# untitled.net
KiCad netlist of a schematic drawn in EAGLE
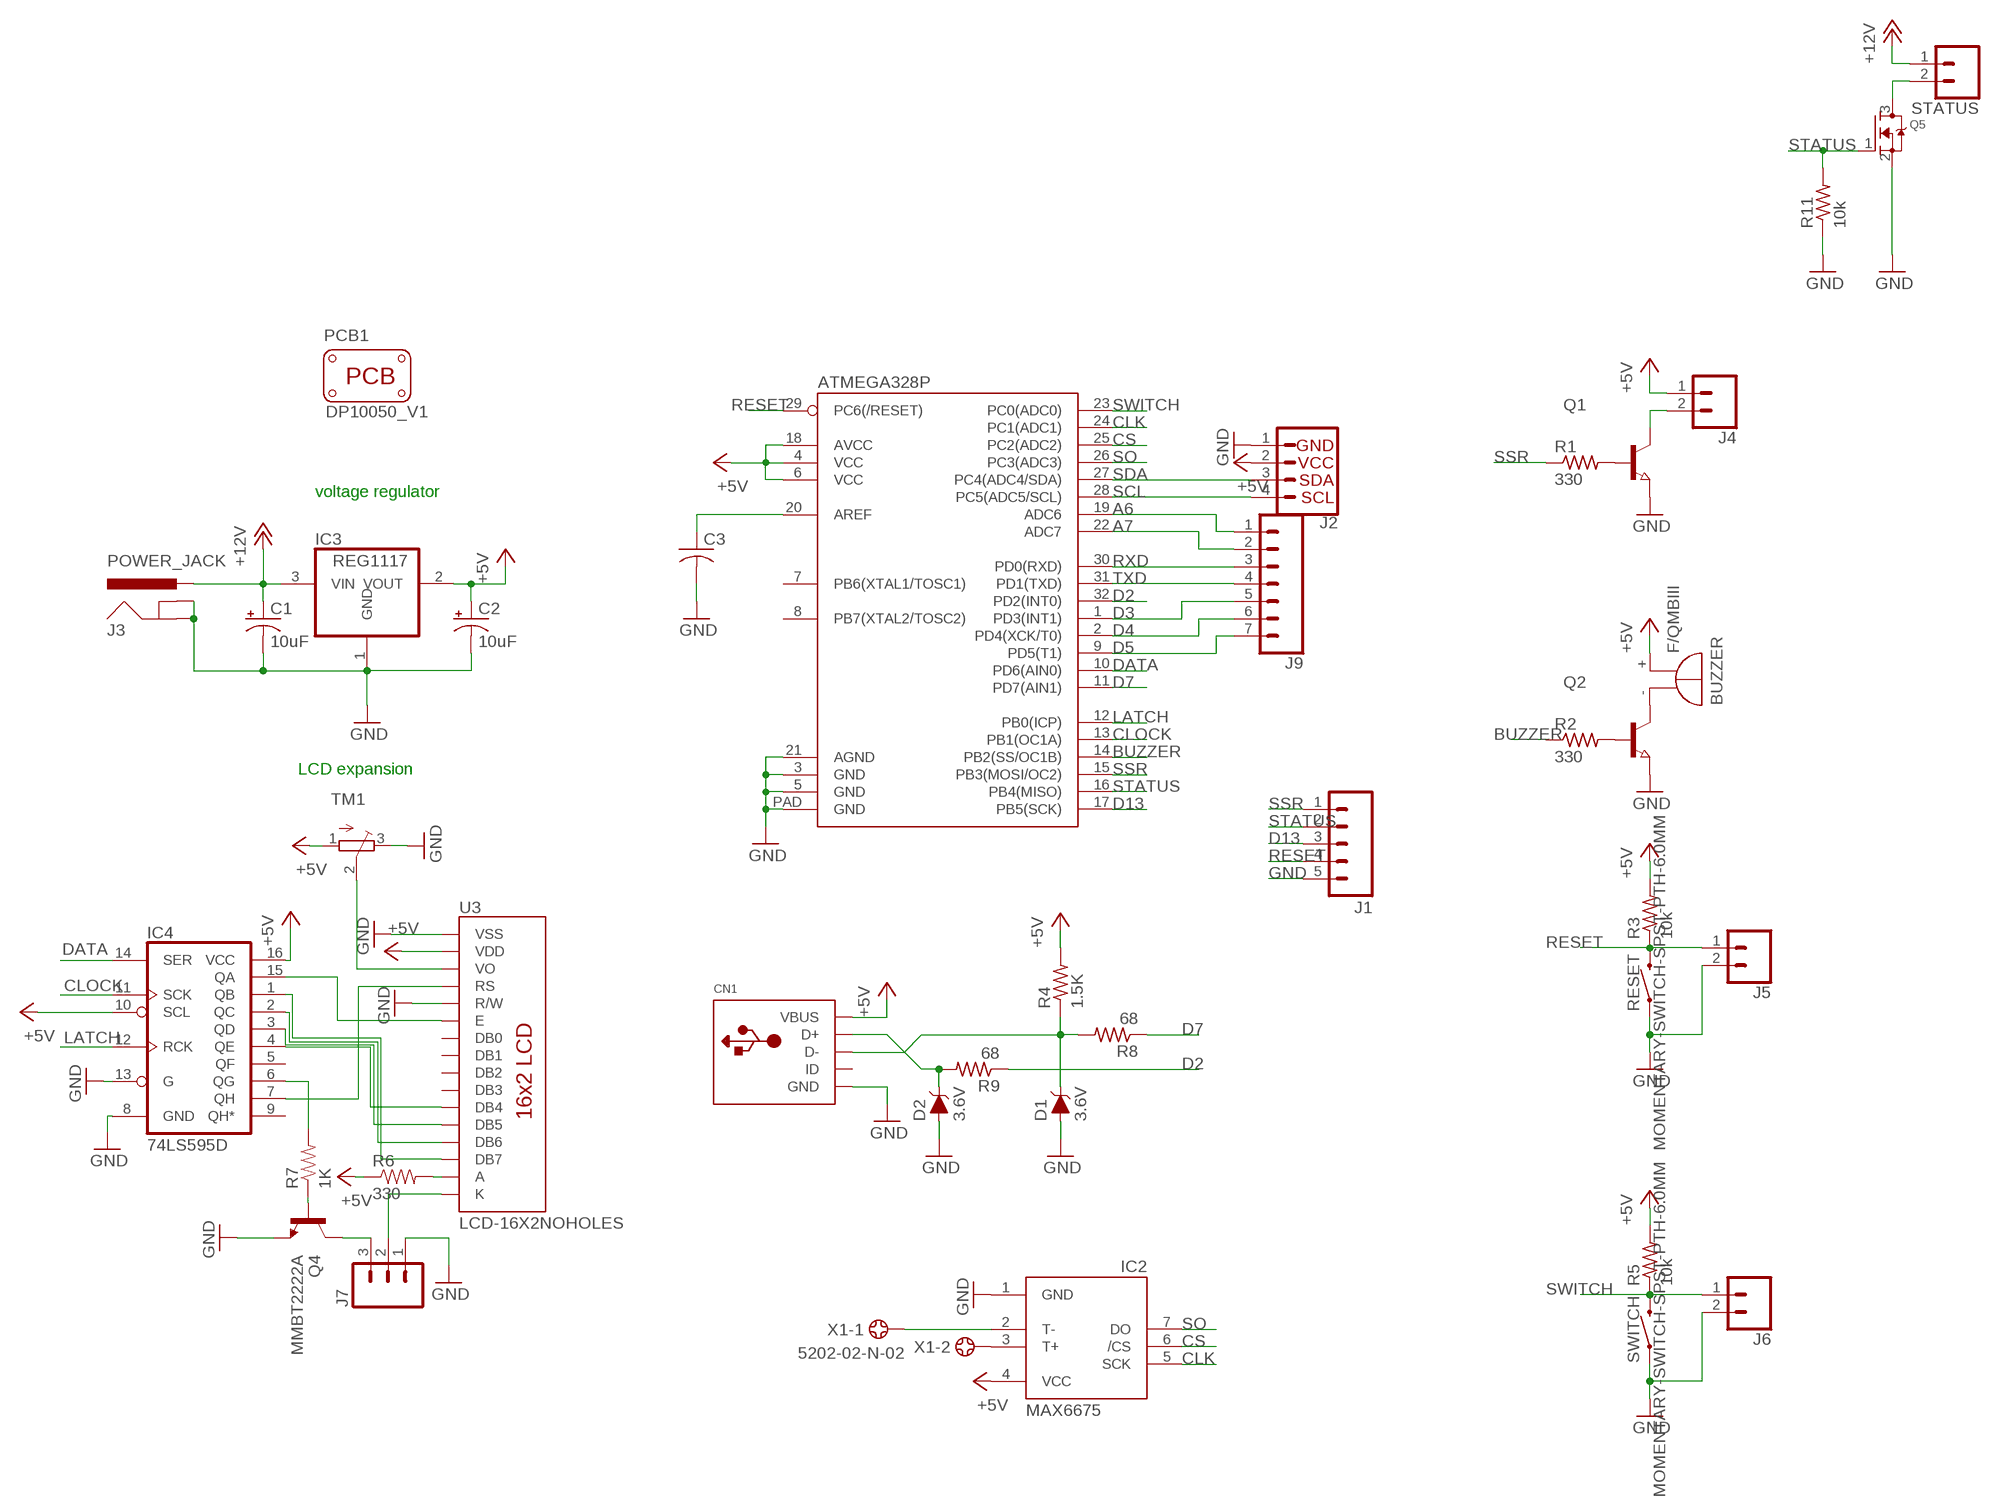
[diagram p0: schematic, sheet 1]

(export (version "E")
  (design (tool "Eeschema 10.0.6"))
  (components
    (comp (ref "ATMEGA328P")
      (value "ATMEGA328P_MLFMLF32")
      (footprint "eagle-import:MLF32-PAD")
      (libsource (lib "eagle-import") (part "ATMEGA328P_MLFMLF32"))
    )
    (comp (ref "BUZZER")
      (value "F/QMBIII")
      (footprint "eagle-import:F_QMBIII")
      (libsource (lib "eagle-import") (part "F/QMBIII"))
    )
    (comp (ref "C1")
      (value "10uF")
      (footprint "eagle-import:CT3216")
      (libsource (lib "eagle-import") (part "CPOL-USCT3216"))
    )
    (comp (ref "C2")
      (value "10uF")
      (footprint "eagle-import:CT3216")
      (libsource (lib "eagle-import") (part "CPOL-USCT3216"))
    )
    (comp (ref "C3")
      (value "C-USC0603")
      (footprint "eagle-import:C0603")
      (libsource (lib "eagle-import") (part "C-USC0603"))
    )
    (comp (ref "CN1")
      (value "USBMINIB")
      (footprint "eagle-import:USB-MINIB")
      (libsource (lib "eagle-import") (part "USBMINIB"))
    )
    (comp (ref "D1")
      (value "3.6V")
      (footprint "eagle-import:SOD-323")
      (libsource (lib "eagle-import") (part "DIODE-ZENER-BZT52C3V6S"))
    )
    (comp (ref "D2")
      (value "3.6V")
      (footprint "eagle-import:SOD-323")
      (libsource (lib "eagle-import") (part "DIODE-ZENER-BZT52C3V6S"))
    )
    (comp (ref "IC2")
      (value "MAX6675")
      (footprint "eagle-import:SO08")
      (libsource (lib "eagle-import") (part "MAX6675"))
    )
    (comp (ref "IC3")
      (value "REG1117")
      (footprint "eagle-import:SOT223")
      (libsource (lib "eagle-import") (part "REG1117"))
    )
    (comp (ref "IC4")
      (value "74LS595D")
      (footprint "eagle-import:SO16")
      (libsource (lib "eagle-import") (part "74595DLS"))
    )
    (comp (ref "J1")
      (value "M051.27MM")
      (footprint "eagle-import:1X05-1.27MM")
      (libsource (lib "eagle-import") (part "M051.27MM"))
    )
    (comp (ref "J2")
      (value "I2C_STANDARD")
      (footprint "eagle-import:1X04")
      (libsource (lib "eagle-import") (part "I2C_STANDARD"))
    )
    (comp (ref "J3")
      (value "POWER_JACK")
      (footprint "eagle-import:POWER_JACK_PTH")
      (libsource (lib "eagle-import") (part "POWER_JACK"))
    )
    (comp (ref "J4")
      (value "CONN_02")
      (footprint "eagle-import:1X02")
      (libsource (lib "eagle-import") (part "CONN_02"))
    )
    (comp (ref "J5")
      (value "CONN_02")
      (footprint "eagle-import:1X02")
      (libsource (lib "eagle-import") (part "CONN_02"))
    )
    (comp (ref "J6")
      (value "CONN_02")
      (footprint "eagle-import:1X02")
      (libsource (lib "eagle-import") (part "CONN_02"))
    )
    (comp (ref "J7")
      (value "M03PTH")
      (footprint "eagle-import:1X03")
      (libsource (lib "eagle-import") (part "M03PTH"))
    )
    (comp (ref "J9")
      (value "CONN_07")
      (footprint "eagle-import:1X07")
      (libsource (lib "eagle-import") (part "CONN_07"))
    )
    (comp (ref "PCB1")
      (value "PCB_DP_RECTANGLE-50X100")
      (footprint "eagle-import:DP10050_V1")
      (libsource (lib "eagle-import") (part "PCB_DP_RECTANGLE-50X100"))
    )
    (comp (ref "Q1")
      (value "NPN-TRANSISTOR_SOT23")
      (footprint "eagle-import:SOT23")
      (libsource (lib "eagle-import") (part "NPN-TRANSISTOR_SOT23"))
    )
    (comp (ref "Q2")
      (value "NPN-TRANSISTOR_SOT23")
      (footprint "eagle-import:SOT23")
      (libsource (lib "eagle-import") (part "NPN-TRANSISTOR_SOT23"))
    )
    (comp (ref "Q4")
      (value "MMBT2222A")
      (footprint "eagle-import:SOT23-3")
      (libsource (lib "eagle-import") (part "TRANSISTOR_NPNMMBT2222A"))
    )
    (comp (ref "Q5")
      (value "MOSFET-NREFLOW")
      (footprint "eagle-import:SOT23")
      (libsource (lib "eagle-import") (part "MOSFET-NREFLOW"))
    )
    (comp (ref "R1")
      (value "330")
      (footprint "eagle-import:R0603")
      (libsource (lib "eagle-import") (part "R-US_R0603"))
    )
    (comp (ref "R2")
      (value "330")
      (footprint "eagle-import:R0603")
      (libsource (lib "eagle-import") (part "R-US_R0603"))
    )
    (comp (ref "R3")
      (value "10k")
      (footprint "eagle-import:R0603")
      (libsource (lib "eagle-import") (part "R-US_R0603"))
    )
    (comp (ref "R4")
      (value "1.5K")
      (footprint "eagle-import:R0603")
      (libsource (lib "eagle-import") (part "R-US_R0603"))
    )
    (comp (ref "R5")
      (value "10k")
      (footprint "eagle-import:R0603")
      (libsource (lib "eagle-import") (part "R-US_R0603"))
    )
    (comp (ref "R6")
      (value "330")
      (footprint "eagle-import:0805")
      (libsource (lib "eagle-import") (part "0.3OHM-1/8W-1%(0805)"))
    )
    (comp (ref "R7")
      (value "1K")
      (footprint "eagle-import:0805")
      (libsource (lib "eagle-import") (part "0.3OHM-1/8W-1%(0805)"))
    )
    (comp (ref "R8")
      (value "68")
      (footprint "eagle-import:R0603")
      (libsource (lib "eagle-import") (part "R-US_R0603"))
    )
    (comp (ref "R9")
      (value "68")
      (footprint "eagle-import:R0603")
      (libsource (lib "eagle-import") (part "R-US_R0603"))
    )
    (comp (ref "R11")
      (value "10k")
      (footprint "eagle-import:R0603")
      (libsource (lib "eagle-import") (part "R-US_R0603"))
    )
    (comp (ref "RESET")
      (value "MOMENTARY-SWITCH-SPST-PTH-6.0MM")
      (footprint "eagle-import:TACTILE_SWITCH_PTH_6.0MM")
      (libsource (lib "eagle-import") (part "MOMENTARY-SWITCH-SPST-PTH-6.0MM"))
    )
    (comp (ref "STATUS")
      (value "CONN_02")
      (footprint "eagle-import:1X02")
      (libsource (lib "eagle-import") (part "CONN_02"))
    )
    (comp (ref "SWITCH")
      (value "MOMENTARY-SWITCH-SPST-PTH-6.0MM")
      (footprint "eagle-import:TACTILE_SWITCH_PTH_6.0MM")
      (libsource (lib "eagle-import") (part "MOMENTARY-SWITCH-SPST-PTH-6.0MM"))
    )
    (comp (ref "TM1")
      (value "TRIMPOT3386")
      (footprint "eagle-import:TRIM-3386")
      (libsource (lib "eagle-import") (part "TRIMPOT3386"))
    )
    (comp (ref "U3")
      (value "LCD-16X2NOHOLES")
      (footprint "eagle-import:LCD-16X2_NOHOLES")
      (libsource (lib "eagle-import") (part "LCD-16X2NOHOLES"))
    )
    (comp (ref "X1")
      (value "5202-02-N-02")
      (footprint "eagle-import:5202-02-N-02")
      (libsource (lib "eagle-import") (part "5202-02-N-02"))
    )
  )
  (nets
    (net (code "1") (name "+5V") (class "Default")
      (node (ref "ATMEGA328P") (pin "18") (pinfunction "AVCC_18") (pintype "bidirectional"))
      (node (ref "ATMEGA328P") (pin "4") (pinfunction "VCC_4") (pintype "bidirectional"))
      (node (ref "ATMEGA328P") (pin "6") (pinfunction "VCC_6") (pintype "bidirectional"))
      (node (ref "BUZZER") (pin "+") (pinfunction "-_+") (pintype "passive"))
      (node (ref "C2") (pin "+") (pinfunction "+_+") (pintype "passive"))
      (node (ref "CN1") (pin "VBUS") (pinfunction "VBUS_VBUS") (pintype "power_in"))
      (node (ref "IC2") (pin "4") (pinfunction "VCC_4") (pintype "power_in"))
      (node (ref "IC3") (pin "2") (pinfunction "VOUT_2") (pintype "output"))
      (node (ref "IC4") (pin "10") (pinfunction "SCL_10") (pintype "input"))
      (node (ref "IC4") (pin "16") (pinfunction "VCC_16") (pintype "power_in"))
      (node (ref "J2") (pin "2") (pinfunction "2_2") (pintype "power_in"))
      (node (ref "J4") (pin "1") (pinfunction "1_1") (pintype "passive"))
      (node (ref "R3") (pin "2") (pinfunction "2_2") (pintype "passive"))
      (node (ref "R4") (pin "2") (pinfunction "2_2") (pintype "passive"))
      (node (ref "R5") (pin "2") (pinfunction "2_2") (pintype "passive"))
      (node (ref "R6") (pin "1") (pinfunction "1_1") (pintype "passive"))
      (node (ref "TM1") (pin "1") (pinfunction "A_1") (pintype "passive"))
      (node (ref "U3") (pin "2") (pinfunction "VDD_2") (pintype "power_in"))
    )
    (net (code "2") (name "+12V") (class "Default")
      (node (ref "C1") (pin "+") (pinfunction "+_+") (pintype "passive"))
      (node (ref "IC3") (pin "3") (pinfunction "VIN_3") (pintype "input"))
      (node (ref "J3") (pin "PWR") (pinfunction "PWR_PWR") (pintype "bidirectional"))
      (node (ref "STATUS") (pin "1") (pinfunction "1_1") (pintype "passive"))
    )
    (net (code "3") (name "/A6") (class "Default")
      (node (ref "ATMEGA328P") (pin "19") (pinfunction "ADC6_19") (pintype "bidirectional"))
      (node (ref "J9") (pin "1") (pinfunction "1_1") (pintype "passive"))
    )
    (net (code "4") (name "/A7") (class "Default")
      (node (ref "ATMEGA328P") (pin "22") (pinfunction "ADC7_22") (pintype "bidirectional"))
      (node (ref "J9") (pin "2") (pinfunction "2_2") (pintype "passive"))
    )
    (net (code "5") (name "/BUZZER") (class "Default")
      (node (ref "ATMEGA328P") (pin "14") (pinfunction "PB2(SS/OC1B)_14") (pintype "bidirectional"))
      (node (ref "R2") (pin "1") (pinfunction "1_1") (pintype "passive"))
    )
    (net (code "6") (name "/CLK") (class "Default")
      (node (ref "ATMEGA328P") (pin "24") (pinfunction "PC1(ADC1)_24") (pintype "bidirectional"))
      (node (ref "IC2") (pin "5") (pinfunction "SCK_5") (pintype "input"))
    )
    (net (code "7") (name "/CLOCK") (class "Default")
      (node (ref "ATMEGA328P") (pin "13") (pinfunction "PB1(OC1A)_13") (pintype "bidirectional"))
      (node (ref "IC4") (pin "11") (pinfunction "SCK_11") (pintype "input"))
    )
    (net (code "8") (name "/CS") (class "Default")
      (node (ref "ATMEGA328P") (pin "25") (pinfunction "PC2(ADC2)_25") (pintype "bidirectional"))
      (node (ref "IC2") (pin "6") (pinfunction "/CS_6") (pintype "input"))
    )
    (net (code "9") (name "/D2") (class "Default")
      (node (ref "ATMEGA328P") (pin "32") (pinfunction "PD2(INT0)_32") (pintype "bidirectional"))
      (node (ref "R9") (pin "1") (pinfunction "1_1") (pintype "passive"))
    )
    (net (code "10") (name "/D3") (class "Default")
      (node (ref "ATMEGA328P") (pin "1") (pinfunction "PD3(INT1)_1") (pintype "bidirectional"))
      (node (ref "J9") (pin "5") (pinfunction "5_5") (pintype "passive"))
    )
    (net (code "11") (name "/D4") (class "Default")
      (node (ref "ATMEGA328P") (pin "2") (pinfunction "PD4(XCK/T0)_2") (pintype "bidirectional"))
      (node (ref "J9") (pin "6") (pinfunction "6_6") (pintype "passive"))
    )
    (net (code "12") (name "/D5") (class "Default")
      (node (ref "ATMEGA328P") (pin "9") (pinfunction "PD5(T1)_9") (pintype "bidirectional"))
      (node (ref "J9") (pin "7") (pinfunction "7_7") (pintype "passive"))
    )
    (net (code "13") (name "/D7") (class "Default")
      (node (ref "ATMEGA328P") (pin "11") (pinfunction "PD7(AIN1)_11") (pintype "bidirectional"))
      (node (ref "R8") (pin "1") (pinfunction "1_1") (pintype "passive"))
    )
    (net (code "14") (name "/D13") (class "Default")
      (node (ref "ATMEGA328P") (pin "17") (pinfunction "PB5(SCK)_17") (pintype "bidirectional"))
      (node (ref "J1") (pin "3") (pinfunction "3_3") (pintype "passive"))
    )
    (net (code "15") (name "/DATA") (class "Default")
      (node (ref "ATMEGA328P") (pin "10") (pinfunction "PD6(AIN0)_10") (pintype "bidirectional"))
      (node (ref "IC4") (pin "14") (pinfunction "SER_14") (pintype "input"))
    )
    (net (code "16") (name "/LATCH") (class "Default")
      (node (ref "ATMEGA328P") (pin "12") (pinfunction "PB0(ICP)_12") (pintype "bidirectional"))
      (node (ref "IC4") (pin "12") (pinfunction "RCK_12") (pintype "input"))
    )
    (net (code "17") (name "/RESET") (class "Default")
      (node (ref "ATMEGA328P") (pin "29") (pinfunction "PC6(/RESET)_29") (pintype "bidirectional"))
      (node (ref "J1") (pin "4") (pinfunction "4_4") (pintype "passive"))
      (node (ref "J5") (pin "1") (pinfunction "1_1") (pintype "passive"))
      (node (ref "R3") (pin "1") (pinfunction "1_1") (pintype "passive"))
      (node (ref "RESET") (pin "3") (pinfunction "2_3") (pintype "passive"))
    )
    (net (code "18") (name "/RXD") (class "Default")
      (node (ref "ATMEGA328P") (pin "30") (pinfunction "PD0(RXD)_30") (pintype "bidirectional"))
      (node (ref "J9") (pin "3") (pinfunction "3_3") (pintype "passive"))
    )
    (net (code "19") (name "/SCL") (class "Default")
      (node (ref "ATMEGA328P") (pin "28") (pinfunction "PC5(ADC5/SCL)_28") (pintype "bidirectional"))
      (node (ref "J2") (pin "4") (pinfunction "4_4") (pintype "passive"))
    )
    (net (code "20") (name "/SDA") (class "Default")
      (node (ref "ATMEGA328P") (pin "27") (pinfunction "PC4(ADC4/SDA)_27") (pintype "bidirectional"))
      (node (ref "J2") (pin "3") (pinfunction "3_3") (pintype "passive"))
    )
    (net (code "21") (name "/SO") (class "Default")
      (node (ref "ATMEGA328P") (pin "26") (pinfunction "PC3(ADC3)_26") (pintype "bidirectional"))
      (node (ref "IC2") (pin "7") (pinfunction "DO_7") (pintype "output"))
    )
    (net (code "22") (name "/SSR") (class "Default")
      (node (ref "ATMEGA328P") (pin "15") (pinfunction "PB3(MOSI/OC2)_15") (pintype "bidirectional"))
      (node (ref "J1") (pin "1") (pinfunction "1_1") (pintype "passive"))
      (node (ref "R1") (pin "1") (pinfunction "1_1") (pintype "passive"))
    )
    (net (code "23") (name "/STATUS") (class "Default")
      (node (ref "ATMEGA328P") (pin "16") (pinfunction "PB4(MISO)_16") (pintype "bidirectional"))
      (node (ref "J1") (pin "2") (pinfunction "2_2") (pintype "passive"))
      (node (ref "Q5") (pin "1") (pinfunction "G_1") (pintype "bidirectional"))
      (node (ref "R11") (pin "2") (pinfunction "2_2") (pintype "passive"))
    )
    (net (code "24") (name "/SWITCH") (class "Default")
      (node (ref "ATMEGA328P") (pin "23") (pinfunction "PC0(ADC0)_23") (pintype "bidirectional"))
      (node (ref "J6") (pin "1") (pinfunction "1_1") (pintype "passive"))
      (node (ref "R5") (pin "1") (pinfunction "1_1") (pintype "passive"))
      (node (ref "SWITCH") (pin "3") (pinfunction "2_3") (pintype "passive"))
    )
    (net (code "25") (name "/TXD") (class "Default")
      (node (ref "ATMEGA328P") (pin "31") (pinfunction "PD1(TXD)_31") (pintype "bidirectional"))
      (node (ref "J9") (pin "4") (pinfunction "4_4") (pintype "passive"))
    )
    (net (code "26") (name "GND") (class "Default")
      (node (ref "ATMEGA328P") (pin "21") (pinfunction "AGND_21") (pintype "bidirectional"))
      (node (ref "ATMEGA328P") (pin "3") (pinfunction "GND_3") (pintype "bidirectional"))
      (node (ref "ATMEGA328P") (pin "5") (pinfunction "GND_5") (pintype "bidirectional"))
      (node (ref "ATMEGA328P") (pin "PAD") (pinfunction "GND_PAD") (pintype "bidirectional"))
      (node (ref "C1") (pin "-") (pinfunction "-_-") (pintype "passive"))
      (node (ref "C2") (pin "-") (pinfunction "-_-") (pintype "passive"))
      (node (ref "C3") (pin "2") (pinfunction "2_2") (pintype "passive"))
      (node (ref "CN1") (pin "GND") (pinfunction "GND_GND") (pintype "power_in"))
      (node (ref "D1") (pin "A") (pinfunction "A_A") (pintype "passive"))
      (node (ref "D2") (pin "A") (pinfunction "A_A") (pintype "passive"))
      (node (ref "IC2") (pin "1") (pinfunction "GND_1") (pintype "power_in"))
      (node (ref "IC3") (pin "1") (pinfunction "GND_1") (pintype "power_in"))
      (node (ref "IC4") (pin "13") (pinfunction "G_13") (pintype "input"))
      (node (ref "IC4") (pin "8") (pinfunction "GND_8") (pintype "power_in"))
      (node (ref "J1") (pin "5") (pinfunction "5_5") (pintype "passive"))
      (node (ref "J2") (pin "1") (pinfunction "1_1") (pintype "power_in"))
      (node (ref "J3") (pin "GND") (pinfunction "GND_GND") (pintype "bidirectional"))
      (node (ref "J3") (pin "GNDBREAK") (pinfunction "GNDBREAK_GNDBREAK") (pintype "bidirectional"))
      (node (ref "J5") (pin "2") (pinfunction "2_2") (pintype "passive"))
      (node (ref "J6") (pin "2") (pinfunction "2_2") (pintype "passive"))
      (node (ref "J7") (pin "1") (pinfunction "1_1") (pintype "passive"))
      (node (ref "Q1") (pin "2") (pinfunction "E_2") (pintype "passive"))
      (node (ref "Q2") (pin "2") (pinfunction "E_2") (pintype "passive"))
      (node (ref "Q4") (pin "2") (pinfunction "E_2") (pintype "passive"))
      (node (ref "Q5") (pin "2") (pinfunction "S_2") (pintype "bidirectional"))
      (node (ref "R11") (pin "1") (pinfunction "1_1") (pintype "passive"))
      (node (ref "RESET") (pin "1") (pinfunction "1_1") (pintype "passive"))
      (node (ref "SWITCH") (pin "1") (pinfunction "1_1") (pintype "passive"))
      (node (ref "TM1") (pin "3") (pinfunction "E_3") (pintype "passive"))
      (node (ref "U3") (pin "1") (pinfunction "VSS_1") (pintype "power_in"))
      (node (ref "U3") (pin "5") (pinfunction "R/W_5") (pintype "input"))
    )
    (net (code "27") (name "Net-(ATMEGA328P-AREF)") (class "Default")
      (node (ref "ATMEGA328P") (pin "20") (pinfunction "AREF_20") (pintype "bidirectional"))
      (node (ref "C3") (pin "1") (pinfunction "1_1") (pintype "passive"))
    )
    (net (code "28") (name "Net-(BUZZER-+)") (class "Default")
      (node (ref "BUZZER") (pin "-") (pinfunction "+_-") (pintype "passive"))
      (node (ref "Q2") (pin "3") (pinfunction "C_3") (pintype "passive"))
    )
    (net (code "29") (name "Net-(CN1-PadD+)") (class "Default")
      (node (ref "CN1") (pin "D+") (pinfunction "D+_D+") (pintype "bidirectional"))
      (node (ref "D2") (pin "C") (pinfunction "C_C") (pintype "passive"))
      (node (ref "R9") (pin "2") (pinfunction "2_2") (pintype "passive"))
    )
    (net (code "30") (name "Net-(CN1-PadD-)") (class "Default")
      (node (ref "CN1") (pin "D-") (pinfunction "D-_D-") (pintype "bidirectional"))
      (node (ref "D1") (pin "C") (pinfunction "C_C") (pintype "passive"))
      (node (ref "R4") (pin "1") (pinfunction "1_1") (pintype "passive"))
      (node (ref "R8") (pin "2") (pinfunction "2_2") (pintype "passive"))
    )
    (net (code "31") (name "Net-(IC2-T+)") (class "Default")
      (node (ref "IC2") (pin "3") (pinfunction "T+_3") (pintype "input"))
      (node (ref "X1") (pin "2") (pinfunction "1_2") (pintype "passive"))
    )
    (net (code "32") (name "Net-(IC2-T-)") (class "Default")
      (node (ref "IC2") (pin "2") (pinfunction "T-_2") (pintype "input"))
      (node (ref "X1") (pin "1") (pinfunction "1_1") (pintype "passive"))
    )
    (net (code "33") (name "Net-(IC4-QA)") (class "Default")
      (node (ref "IC4") (pin "15") (pinfunction "QA_15") (pintype "tri_state"))
      (node (ref "U3") (pin "6") (pinfunction "E_6") (pintype "input"))
    )
    (net (code "34") (name "Net-(IC4-QB)") (class "Default")
      (node (ref "IC4") (pin "1") (pinfunction "QB_1") (pintype "tri_state"))
      (node (ref "U3") (pin "14") (pinfunction "DB7_14") (pintype "bidirectional"))
    )
    (net (code "35") (name "Net-(IC4-QC)") (class "Default")
      (node (ref "IC4") (pin "2") (pinfunction "QC_2") (pintype "tri_state"))
      (node (ref "U3") (pin "13") (pinfunction "DB6_13") (pintype "bidirectional"))
    )
    (net (code "36") (name "Net-(IC4-QD)") (class "Default")
      (node (ref "IC4") (pin "3") (pinfunction "QD_3") (pintype "tri_state"))
      (node (ref "U3") (pin "12") (pinfunction "DB5_12") (pintype "bidirectional"))
    )
    (net (code "37") (name "Net-(IC4-QE)") (class "Default")
      (node (ref "IC4") (pin "4") (pinfunction "QE_4") (pintype "tri_state"))
      (node (ref "U3") (pin "11") (pinfunction "DB4_11") (pintype "bidirectional"))
    )
    (net (code "38") (name "Net-(IC4-QG)") (class "Default")
      (node (ref "IC4") (pin "6") (pinfunction "QG_6") (pintype "tri_state"))
      (node (ref "R7") (pin "2") (pinfunction "2_2") (pintype "passive"))
    )
    (net (code "39") (name "Net-(IC4-QH)") (class "Default")
      (node (ref "IC4") (pin "7") (pinfunction "QH_7") (pintype "tri_state"))
      (node (ref "U3") (pin "4") (pinfunction "RS_4") (pintype "input"))
    )
    (net (code "40") (name "Net-(Q1-B)") (class "Default")
      (node (ref "Q1") (pin "1") (pinfunction "B_1") (pintype "passive"))
      (node (ref "R1") (pin "2") (pinfunction "2_2") (pintype "passive"))
    )
    (net (code "41") (name "Net-(Q1-C)") (class "Default")
      (node (ref "J4") (pin "2") (pinfunction "2_2") (pintype "passive"))
      (node (ref "Q1") (pin "3") (pinfunction "C_3") (pintype "passive"))
    )
    (net (code "42") (name "Net-(Q2-B)") (class "Default")
      (node (ref "Q2") (pin "1") (pinfunction "B_1") (pintype "passive"))
      (node (ref "R2") (pin "2") (pinfunction "2_2") (pintype "passive"))
    )
    (net (code "43") (name "Net-(Q4-B)") (class "Default")
      (node (ref "Q4") (pin "1") (pinfunction "B_1") (pintype "passive"))
      (node (ref "R7") (pin "1") (pinfunction "1_1") (pintype "passive"))
    )
    (net (code "44") (name "Net-(Q4-C)") (class "Default")
      (node (ref "J7") (pin "3") (pinfunction "3_3") (pintype "passive"))
      (node (ref "Q4") (pin "3") (pinfunction "C_3") (pintype "passive"))
    )
    (net (code "45") (name "Net-(Q5-D)") (class "Default")
      (node (ref "Q5") (pin "3") (pinfunction "D_3") (pintype "bidirectional"))
      (node (ref "STATUS") (pin "2") (pinfunction "2_2") (pintype "passive"))
    )
    (net (code "46") (name "Net-(TM1-S)") (class "Default")
      (node (ref "TM1") (pin "2") (pinfunction "S_2") (pintype "passive"))
      (node (ref "U3") (pin "3") (pinfunction "VO_3") (pintype "bidirectional"))
    )
    (net (code "47") (name "Net-(U3-A)") (class "Default")
      (node (ref "R6") (pin "2") (pinfunction "2_2") (pintype "passive"))
      (node (ref "U3") (pin "15") (pinfunction "A_15") (pintype "power_in"))
    )
    (net (code "48") (name "Net-(U3-K)") (class "Default")
      (node (ref "J7") (pin "2") (pinfunction "2_2") (pintype "passive"))
      (node (ref "U3") (pin "16") (pinfunction "K_16") (pintype "power_in"))
    )
    (net (code "49") (name "unconnected-(ATMEGA328P-PB6(XTAL1{slash}TOSC1)-Pad7)") (class "Default")
      (node (ref "ATMEGA328P") (pin "7") (pinfunction "PB6(XTAL1/TOSC1)_7") (pintype "bidirectional"))
    )
    (net (code "50") (name "unconnected-(ATMEGA328P-PB7(XTAL2{slash}TOSC2)-Pad8)") (class "Default")
      (node (ref "ATMEGA328P") (pin "8") (pinfunction "PB7(XTAL2/TOSC2)_8") (pintype "bidirectional"))
    )
    (net (code "51") (name "unconnected-(CN1-PadID)") (class "Default")
      (node (ref "CN1") (pin "ID") (pinfunction "ID_ID") (pintype "bidirectional"))
    )
    (net (code "52") (name "unconnected-(IC4-QF-Pad5)") (class "Default")
      (node (ref "IC4") (pin "5") (pinfunction "QF_5") (pintype "tri_state"))
    )
    (net (code "53") (name "unconnected-(IC4-QH*-Pad9)") (class "Default")
      (node (ref "IC4") (pin "9") (pinfunction "QH*_9") (pintype "tri_state"))
    )
    (net (code "54") (name "unconnected-(U3-DB0-Pad7)") (class "Default")
      (node (ref "U3") (pin "7") (pinfunction "DB0_7") (pintype "bidirectional"))
    )
    (net (code "55") (name "unconnected-(U3-DB1-Pad8)") (class "Default")
      (node (ref "U3") (pin "8") (pinfunction "DB1_8") (pintype "bidirectional"))
    )
    (net (code "56") (name "unconnected-(U3-DB2-Pad9)") (class "Default")
      (node (ref "U3") (pin "9") (pinfunction "DB2_9") (pintype "bidirectional"))
    )
    (net (code "57") (name "unconnected-(U3-DB3-Pad10)") (class "Default")
      (node (ref "U3") (pin "10") (pinfunction "DB3_10") (pintype "bidirectional"))
    )
  )
)
